# Serial_Sniffer.net
KiCad netlist of a schematic drawn in Altium Designer
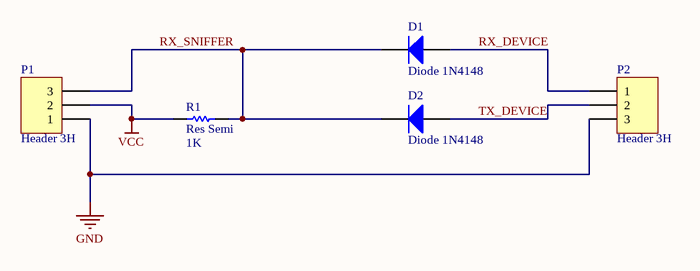
[diagram p0: Serial_Sniffer.SchDoc]

(export (version "E")
  (design (tool "Eeschema 10.0.6"))
  (components
    (comp (ref "D1")
      (value "Diode 1N4148")
      (footprint "DO-35")
      (description "High Conductance Fast Diode")
      (fields (field (name "PUBLISHER") "Altium Limited"))
      (libsource (lib "Miscellaneous Devices") (part "Diode 1N4148"))
    )
    (comp (ref "D2")
      (value "Diode 1N4148")
      (footprint "DO-35")
      (description "High Conductance Fast Diode")
      (fields (field (name "PUBLISHER") "Altium Limited"))
      (libsource (lib "Miscellaneous Devices") (part "Diode 1N4148"))
    )
    (comp (ref "P1")
      (value "Header 3H")
      (footprint "HDR1X3H")
      (description "Header, 3-Pin, Right Angle")
      (fields (field (name "PUBLISHER") "Altium Limited"))
      (libsource (lib "") (part "Header 3H_1"))
    )
    (comp (ref "P2")
      (value "Header 3H")
      (footprint "HDR1X3H")
      (description "Header, 3-Pin, Right Angle")
      (fields (field (name "PUBLISHER") "Altium Limited"))
      (libsource (lib "Miscellaneous Connectors") (part "Header 3H"))
    )
    (comp (ref "R1")
      (value "Res Semi")
      (footprint "AXIAL-0.5")
      (description "Semiconductor Resistor")
      (fields (field (name "ALTIUM_VALUE") "1K") (field (name "PUBLISHER") "Altium Limited"))
      (libsource (lib "Miscellaneous Devices") (part "Res Semi"))
    )
  )
  (nets
    (net (code "1") (name "/RX_DEVICE") (class "Default")
      (node (ref "D1") (pin "1") (pinfunction "A_1") (pintype "passive"))
      (node (ref "P2") (pin "1") (pinfunction "1_1") (pintype "passive"))
    )
    (net (code "2") (name "/RX_SNIFFER") (class "Default")
      (node (ref "D1") (pin "2") (pinfunction "K_2") (pintype "passive"))
      (node (ref "D2") (pin "2") (pinfunction "K_2") (pintype "passive"))
      (node (ref "P1") (pin "3") (pinfunction "3_3") (pintype "passive"))
      (node (ref "R1") (pin "2") (pinfunction "2_2") (pintype "passive"))
    )
    (net (code "3") (name "/TX_DEVICE") (class "Default")
      (node (ref "D2") (pin "1") (pinfunction "A_1") (pintype "passive"))
      (node (ref "P2") (pin "2") (pinfunction "2_2") (pintype "passive"))
    )
    (net (code "4") (name "GND") (class "Default")
      (node (ref "P1") (pin "1") (pinfunction "1_1") (pintype "passive"))
      (node (ref "P2") (pin "3") (pinfunction "3_3") (pintype "passive"))
    )
    (net (code "5") (name "VCC") (class "Default")
      (node (ref "P1") (pin "2") (pinfunction "2_2") (pintype "passive"))
      (node (ref "R1") (pin "1") (pinfunction "1_1") (pintype "passive"))
    )
  )
)
